# led-bike-suit-controller_v2.net
KiCad netlist of a schematic drawn in EAGLE
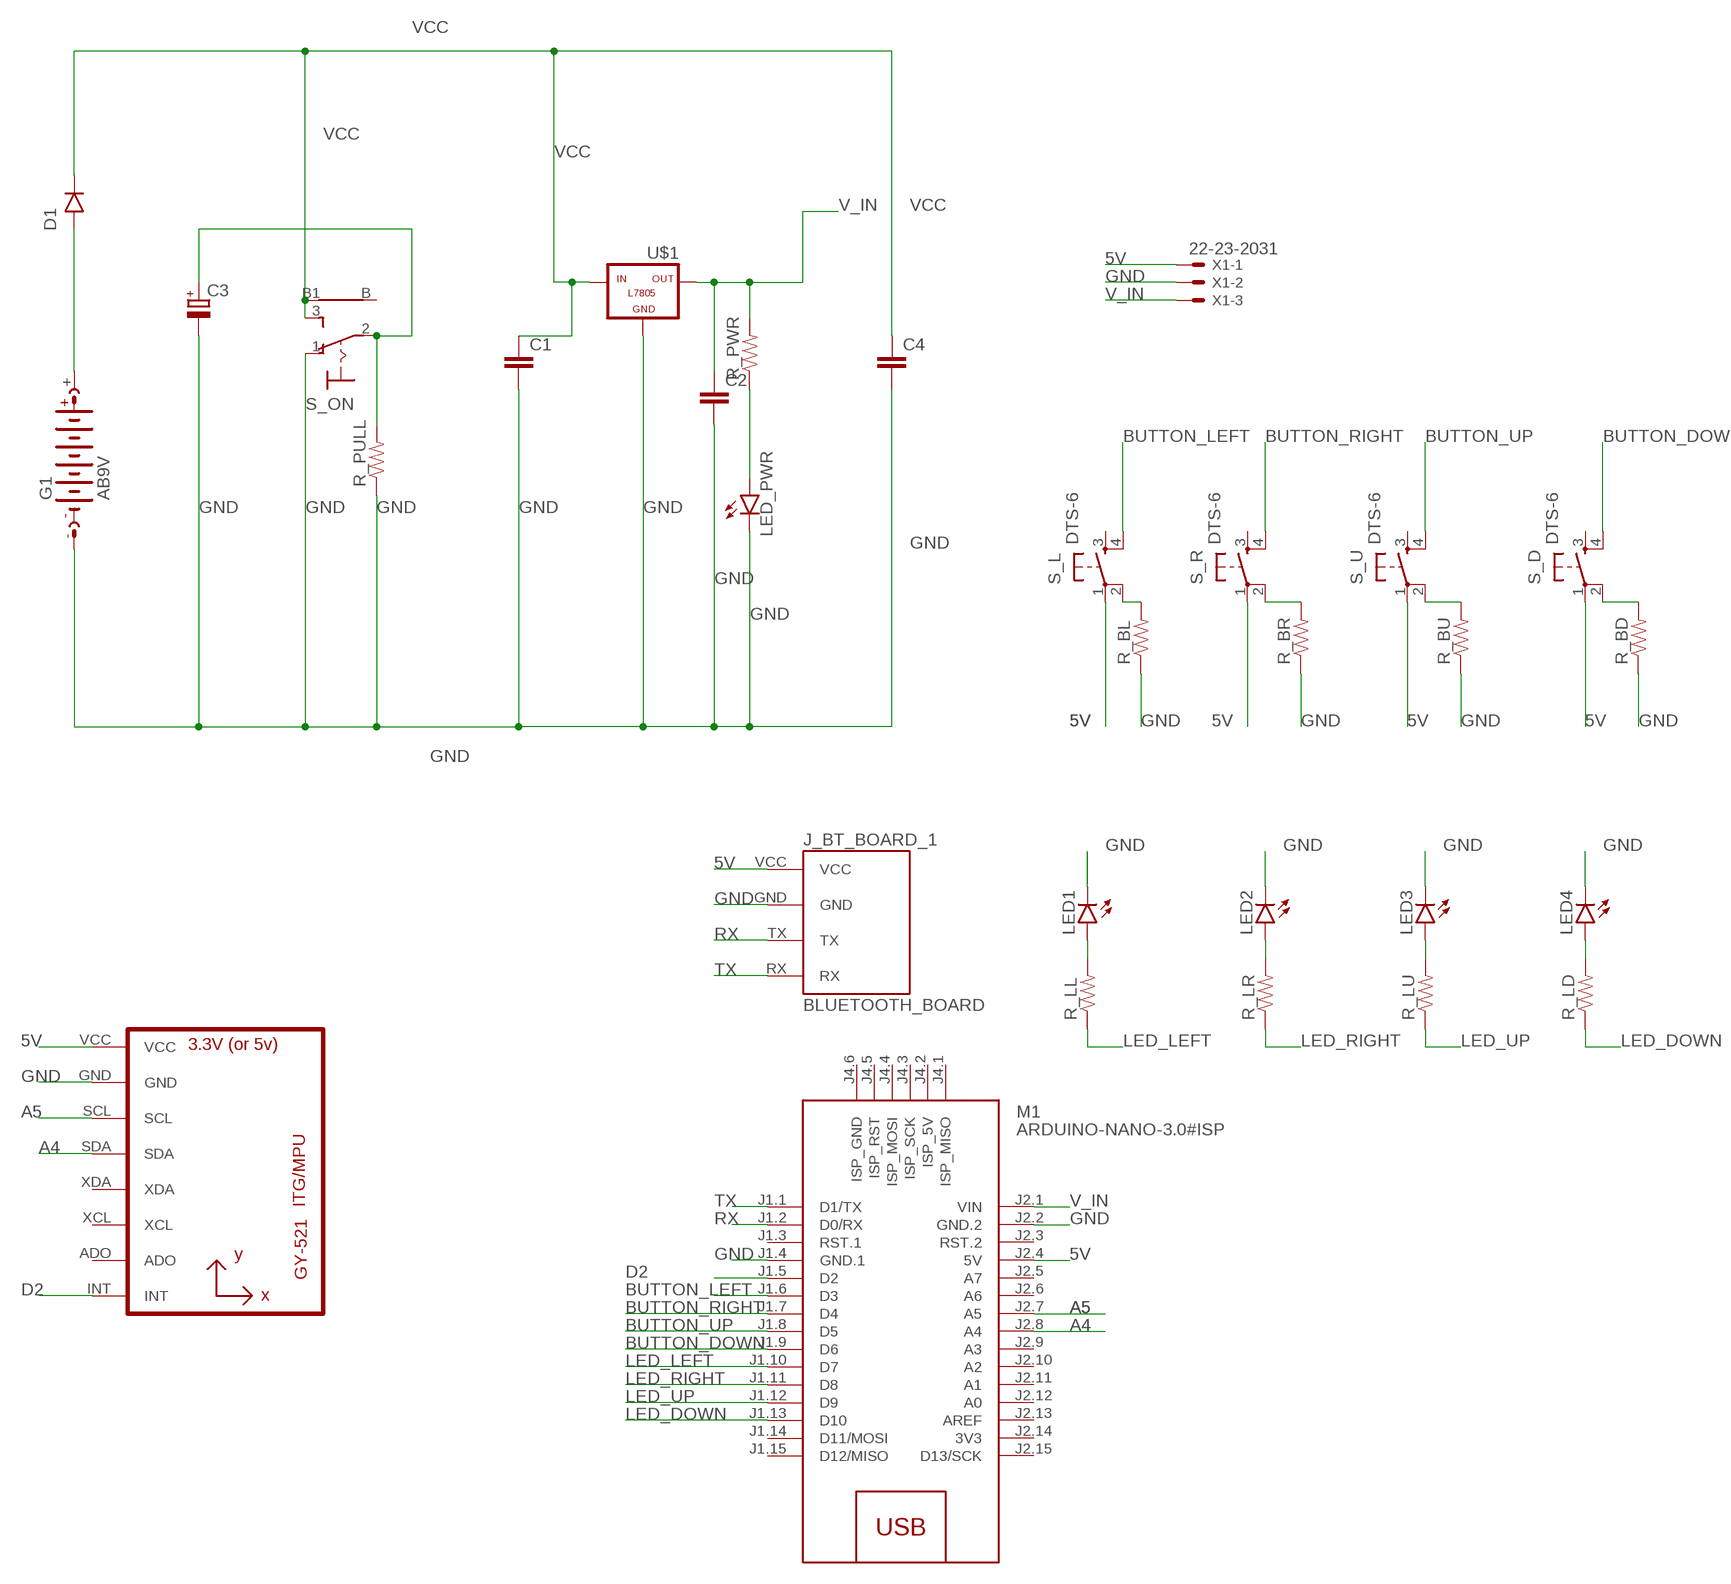
[diagram p0: schematic, sheet 1]

(export (version "E")
  (design (tool "Eeschema 10.0.6"))
  (components
    (comp (ref "C1")
      (value "C2.5/4")
      (footprint "eagle-import:C2.5-4")
      (libsource (lib "eagle-import") (part "C2.5/4"))
    )
    (comp (ref "C2")
      (value "C2.5/4")
      (footprint "eagle-import:C2.5-4")
      (libsource (lib "eagle-import") (part "C2.5/4"))
    )
    (comp (ref "C3")
      (value "RCL_CPOL-EUE3.5-8")
      (footprint "eagle-import:ELECTROLYTIC_CAP_RCL_E3,5-8")
      (libsource (lib "eagle-import") (part "RCL_CPOL-EUE3.5-8"))
    )
    (comp (ref "C4")
      (value "C2.5/4")
      (footprint "eagle-import:C2.5-4")
      (libsource (lib "eagle-import") (part "C2.5/4"))
    )
    (comp (ref "D1")
      (value "1N4001")
      (footprint "eagle-import:DO41-10")
      (libsource (lib "eagle-import") (part "1N4001"))
    )
    (comp (ref "G1")
      (value "AB9V")
      (footprint "eagle-import:AB9V")
      (libsource (lib "eagle-import") (part "AB9V"))
    )
    (comp (ref "J_BT_BOARD_1")
      (value "BLUETOOTH_BOARD")
      (footprint "eagle-import:BT_BOARD_FOOTPRINT")
      (libsource (lib "eagle-import") (part "BLUETOOTH_BOARD"))
    )
    (comp (ref "LED1")
      (value "LED5MM")
      (footprint "eagle-import:SPARKFUN-LED_LED5MM")
      (libsource (lib "eagle-import") (part "LED5MM"))
    )
    (comp (ref "LED2")
      (value "LED5MM")
      (footprint "eagle-import:SPARKFUN-LED_LED5MM")
      (libsource (lib "eagle-import") (part "LED5MM"))
    )
    (comp (ref "LED3")
      (value "LED5MM")
      (footprint "eagle-import:SPARKFUN-LED_LED5MM")
      (libsource (lib "eagle-import") (part "LED5MM"))
    )
    (comp (ref "LED4")
      (value "LED5MM")
      (footprint "eagle-import:SPARKFUN-LED_LED5MM")
      (libsource (lib "eagle-import") (part "LED5MM"))
    )
    (comp (ref "LED_PWR")
      (value "LED5MM")
      (footprint "eagle-import:LED5MM")
      (libsource (lib "eagle-import") (part "tango_LED5MM"))
    )
    (comp (ref "M1")
      (value "ARDUINO-NANO-3.0#ISP")
      (footprint "eagle-import:ARDUINO-NANO-3.0#ISP")
      (libsource (lib "eagle-import") (part "ARDUINO-NANO-3.0#ISP"))
    )
    (comp (ref "R_BD")
      (value "PASSIVES_RESISTORPTH-1/4W")
      (footprint "eagle-import:SPARKFUN-PASSIVES_AXIAL-0.4")
      (libsource (lib "eagle-import") (part "PASSIVES_RESISTORPTH-1/4W"))
    )
    (comp (ref "R_BL")
      (value "PASSIVES_RESISTORPTH-1/4W")
      (footprint "eagle-import:SPARKFUN-PASSIVES_AXIAL-0.4")
      (libsource (lib "eagle-import") (part "PASSIVES_RESISTORPTH-1/4W"))
    )
    (comp (ref "R_BR")
      (value "PASSIVES_RESISTORPTH-1/4W")
      (footprint "eagle-import:SPARKFUN-PASSIVES_AXIAL-0.4")
      (libsource (lib "eagle-import") (part "PASSIVES_RESISTORPTH-1/4W"))
    )
    (comp (ref "R_BU")
      (value "PASSIVES_RESISTORPTH-1/4W")
      (footprint "eagle-import:SPARKFUN-PASSIVES_AXIAL-0.4")
      (libsource (lib "eagle-import") (part "PASSIVES_RESISTORPTH-1/4W"))
    )
    (comp (ref "R_LD")
      (value "PASSIVES_RESISTORPTH-1/4W")
      (footprint "eagle-import:SPARKFUN-PASSIVES_AXIAL-0.4")
      (libsource (lib "eagle-import") (part "PASSIVES_RESISTORPTH-1/4W"))
    )
    (comp (ref "R_LL")
      (value "PASSIVES_RESISTORPTH-1/4W")
      (footprint "eagle-import:SPARKFUN-PASSIVES_AXIAL-0.4")
      (libsource (lib "eagle-import") (part "PASSIVES_RESISTORPTH-1/4W"))
    )
    (comp (ref "R_LR")
      (value "PASSIVES_RESISTORPTH-1/4W")
      (footprint "eagle-import:SPARKFUN-PASSIVES_AXIAL-0.4")
      (libsource (lib "eagle-import") (part "PASSIVES_RESISTORPTH-1/4W"))
    )
    (comp (ref "R_LU")
      (value "PASSIVES_RESISTORPTH-1/4W")
      (footprint "eagle-import:SPARKFUN-PASSIVES_AXIAL-0.4")
      (libsource (lib "eagle-import") (part "PASSIVES_RESISTORPTH-1/4W"))
    )
    (comp (ref "R_PULL")
      (value "PASSIVES_RESISTORPTH-1/4W")
      (footprint "eagle-import:SPARKFUN-PASSIVES_AXIAL-0.4")
      (libsource (lib "eagle-import") (part "PASSIVES_RESISTORPTH-1/4W"))
    )
    (comp (ref "R_PWR")
      (value "PASSIVES_RESISTORPTH-1/4W")
      (footprint "eagle-import:SPARKFUN-PASSIVES_AXIAL-0.4")
      (libsource (lib "eagle-import") (part "PASSIVES_RESISTORPTH-1/4W"))
    )
    (comp (ref "S_D")
      (value "DTS-6")
      (footprint "eagle-import:DTS-6")
      (libsource (lib "eagle-import") (part "DTS-6"))
    )
    (comp (ref "S_L")
      (value "DTS-6")
      (footprint "eagle-import:DTS-6")
      (libsource (lib "eagle-import") (part "DTS-6"))
    )
    (comp (ref "S_ON")
      (value "9070-1W")
      (footprint "eagle-import:9070-1W")
      (libsource (lib "eagle-import") (part "9070-1W"))
    )
    (comp (ref "S_R")
      (value "DTS-6")
      (footprint "eagle-import:DTS-6")
      (libsource (lib "eagle-import") (part "DTS-6"))
    )
    (comp (ref "S_U")
      (value "DTS-6")
      (footprint "eagle-import:DTS-6")
      (libsource (lib "eagle-import") (part "DTS-6"))
    )
    (comp (ref "U$1")
      (value "-L7805")
      (footprint "eagle-import:L7805")
      (libsource (lib "eagle-import") (part "-L7805"))
    )
    (comp (ref "U1")
      (value "GY-521MPU6050")
      (footprint "eagle-import:GY-521")
      (libsource (lib "eagle-import") (part "GY-521MPU6050"))
    )
    (comp (ref "X1")
      (value "22-23-2031")
      (footprint "eagle-import:22-23-2031")
      (fields (field (name "MF") "MOLEX"))
      (libsource (lib "eagle-import") (part "22-23-2031"))
    )
  )
  (nets
    (net (code "1") (name "/3V3") (class "Default")
      (node (ref "M1") (pin "J2.14") (pinfunction "3V3_J2.14") (pintype "power_in"))
    )
    (net (code "2") (name "/5V") (class "Default")
      (node (ref "J_BT_BOARD_1") (pin "VCC") (pinfunction "VCC_VCC") (pintype "bidirectional"))
      (node (ref "M1") (pin "J2.4") (pinfunction "5V_J2.4") (pintype "power_in"))
      (node (ref "S_D") (pin "1") (pinfunction "1_1") (pintype "passive"))
      (node (ref "S_L") (pin "1") (pinfunction "1_1") (pintype "passive"))
      (node (ref "S_R") (pin "1") (pinfunction "1_1") (pintype "passive"))
      (node (ref "S_U") (pin "1") (pinfunction "1_1") (pintype "passive"))
      (node (ref "U1") (pin "VCC") (pinfunction "VCC_VCC") (pintype "bidirectional"))
      (node (ref "X1") (pin "1") (pinfunction "S_1") (pintype "passive"))
    )
    (net (code "3") (name "/A4") (class "Default")
      (node (ref "M1") (pin "J2.8") (pinfunction "A4_J2.8") (pintype "bidirectional"))
      (node (ref "U1") (pin "SDA") (pinfunction "SDA_SDA") (pintype "bidirectional"))
    )
    (net (code "4") (name "/A5") (class "Default")
      (node (ref "M1") (pin "J2.7") (pinfunction "A5_J2.7") (pintype "bidirectional"))
      (node (ref "U1") (pin "SCL") (pinfunction "SCL_SCL") (pintype "bidirectional"))
    )
    (net (code "5") (name "/BUTTON_DOWN") (class "Default")
      (node (ref "M1") (pin "J1.9") (pinfunction "D6_J1.9") (pintype "bidirectional"))
      (node (ref "S_D") (pin "4") (pinfunction "4_4") (pintype "passive"))
    )
    (net (code "6") (name "/BUTTON_LEFT") (class "Default")
      (node (ref "M1") (pin "J1.6") (pinfunction "D3_J1.6") (pintype "bidirectional"))
      (node (ref "S_L") (pin "4") (pinfunction "4_4") (pintype "passive"))
    )
    (net (code "7") (name "/BUTTON_RIGHT") (class "Default")
      (node (ref "M1") (pin "J1.7") (pinfunction "D4_J1.7") (pintype "bidirectional"))
      (node (ref "S_R") (pin "4") (pinfunction "4_4") (pintype "passive"))
    )
    (net (code "8") (name "/BUTTON_UP") (class "Default")
      (node (ref "M1") (pin "J1.8") (pinfunction "D5_J1.8") (pintype "bidirectional"))
      (node (ref "S_U") (pin "4") (pinfunction "4_4") (pintype "passive"))
    )
    (net (code "9") (name "/D2") (class "Default")
      (node (ref "M1") (pin "J1.5") (pinfunction "D2_J1.5") (pintype "bidirectional"))
      (node (ref "U1") (pin "INT") (pinfunction "INT_INT") (pintype "bidirectional"))
    )
    (net (code "10") (name "/GND") (class "Default")
      (node (ref "C1") (pin "2") (pinfunction "2_2") (pintype "passive"))
      (node (ref "C2") (pin "2") (pinfunction "2_2") (pintype "passive"))
      (node (ref "C3") (pin "-") (pinfunction "-_-") (pintype "passive"))
      (node (ref "C4") (pin "2") (pinfunction "2_2") (pintype "passive"))
      (node (ref "G1") (pin "-") (pinfunction "-_-") (pintype "passive"))
      (node (ref "J_BT_BOARD_1") (pin "GND") (pinfunction "GND_GND") (pintype "bidirectional"))
      (node (ref "LED1") (pin "K") (pinfunction "C_K") (pintype "passive"))
      (node (ref "LED2") (pin "K") (pinfunction "C_K") (pintype "passive"))
      (node (ref "LED3") (pin "K") (pinfunction "C_K") (pintype "passive"))
      (node (ref "LED4") (pin "K") (pinfunction "C_K") (pintype "passive"))
      (node (ref "LED_PWR") (pin "K") (pinfunction "CATHODE_K") (pintype "passive"))
      (node (ref "M1") (pin "J1.4") (pinfunction "GND.1_J1.4") (pintype "power_in"))
      (node (ref "M1") (pin "J2.2") (pinfunction "GND.2_J2.2") (pintype "power_in"))
      (node (ref "R_BD") (pin "P$1") (pinfunction "1_P$1") (pintype "passive"))
      (node (ref "R_BL") (pin "P$1") (pinfunction "1_P$1") (pintype "passive"))
      (node (ref "R_BR") (pin "P$1") (pinfunction "1_P$1") (pintype "passive"))
      (node (ref "R_BU") (pin "P$1") (pinfunction "1_P$1") (pintype "passive"))
      (node (ref "R_PULL") (pin "P$1") (pinfunction "1_P$1") (pintype "passive"))
      (node (ref "S_ON") (pin "1") (pinfunction "O_1") (pintype "passive"))
      (node (ref "U$1") (pin "GND") (pinfunction "GND_GND") (pintype "input"))
      (node (ref "U1") (pin "GND") (pinfunction "GND_GND") (pintype "bidirectional"))
      (node (ref "X1") (pin "2") (pinfunction "S_2") (pintype "passive"))
    )
    (net (code "11") (name "/LED_DOWN") (class "Default")
      (node (ref "M1") (pin "J1.13") (pinfunction "D10_J1.13") (pintype "bidirectional"))
      (node (ref "R_LD") (pin "P$1") (pinfunction "1_P$1") (pintype "passive"))
    )
    (net (code "12") (name "/LED_LEFT") (class "Default")
      (node (ref "M1") (pin "J1.10") (pinfunction "D7_J1.10") (pintype "bidirectional"))
      (node (ref "R_LL") (pin "P$1") (pinfunction "1_P$1") (pintype "passive"))
    )
    (net (code "13") (name "/LED_RIGHT") (class "Default")
      (node (ref "M1") (pin "J1.11") (pinfunction "D8_J1.11") (pintype "bidirectional"))
      (node (ref "R_LR") (pin "P$1") (pinfunction "1_P$1") (pintype "passive"))
    )
    (net (code "14") (name "/LED_UP") (class "Default")
      (node (ref "M1") (pin "J1.12") (pinfunction "D9_J1.12") (pintype "bidirectional"))
      (node (ref "R_LU") (pin "P$1") (pinfunction "1_P$1") (pintype "passive"))
    )
    (net (code "15") (name "/RX") (class "Default")
      (node (ref "J_BT_BOARD_1") (pin "TX") (pinfunction "TX_TX") (pintype "bidirectional"))
      (node (ref "M1") (pin "J1.2") (pinfunction "D0/RX_J1.2") (pintype "bidirectional"))
    )
    (net (code "16") (name "/TX") (class "Default")
      (node (ref "J_BT_BOARD_1") (pin "RX") (pinfunction "RX_RX") (pintype "bidirectional"))
      (node (ref "M1") (pin "J1.1") (pinfunction "D1/TX_J1.1") (pintype "bidirectional"))
    )
    (net (code "17") (name "/VCC") (class "Default")
      (node (ref "C1") (pin "1") (pinfunction "1_1") (pintype "passive"))
      (node (ref "C4") (pin "1") (pinfunction "1_1") (pintype "passive"))
      (node (ref "D1") (pin "C") (pinfunction "CATHODE_C") (pintype "passive"))
      (node (ref "S_ON") (pin "3") (pinfunction "S_3") (pintype "passive"))
      (node (ref "S_ON") (pin "B1") (pinfunction "B1_B1") (pintype "passive"))
      (node (ref "U$1") (pin "IN") (pinfunction "IN_IN") (pintype "input"))
    )
    (net (code "18") (name "/V_IN") (class "Default")
      (node (ref "C2") (pin "1") (pinfunction "1_1") (pintype "passive"))
      (node (ref "M1") (pin "J2.1") (pinfunction "VIN_J2.1") (pintype "power_in"))
      (node (ref "R_PWR") (pin "P$2") (pinfunction "2_P$2") (pintype "passive"))
      (node (ref "U$1") (pin "OUT") (pinfunction "OUT_OUT") (pintype "passive"))
      (node (ref "X1") (pin "3") (pinfunction "S_3") (pintype "passive"))
    )
    (net (code "19") (name "Net-(D1-ANODE)") (class "Default")
      (node (ref "D1") (pin "A") (pinfunction "ANODE_A") (pintype "passive"))
      (node (ref "G1") (pin "+") (pinfunction "+_+") (pintype "passive"))
    )
    (net (code "20") (name "Net-(LED_PWR-ANODE)") (class "Default")
      (node (ref "LED_PWR") (pin "A") (pinfunction "ANODE_A") (pintype "passive"))
      (node (ref "R_PWR") (pin "P$1") (pinfunction "1_P$1") (pintype "passive"))
    )
    (net (code "21") (name "Net-(R_BD-2)") (class "Default")
      (node (ref "R_BD") (pin "P$2") (pinfunction "2_P$2") (pintype "passive"))
      (node (ref "S_D") (pin "2") (pinfunction "2_2") (pintype "passive"))
    )
    (net (code "22") (name "Net-(R_BL-2)") (class "Default")
      (node (ref "R_BL") (pin "P$2") (pinfunction "2_P$2") (pintype "passive"))
      (node (ref "S_L") (pin "2") (pinfunction "2_2") (pintype "passive"))
    )
    (net (code "23") (name "Net-(R_BR-2)") (class "Default")
      (node (ref "R_BR") (pin "P$2") (pinfunction "2_P$2") (pintype "passive"))
      (node (ref "S_R") (pin "2") (pinfunction "2_2") (pintype "passive"))
    )
    (net (code "24") (name "Net-(R_BU-2)") (class "Default")
      (node (ref "R_BU") (pin "P$2") (pinfunction "2_P$2") (pintype "passive"))
      (node (ref "S_U") (pin "2") (pinfunction "2_2") (pintype "passive"))
    )
    (net (code "25") (name "Net-(R_LD-2)") (class "Default")
      (node (ref "LED4") (pin "A") (pinfunction "A_A") (pintype "passive"))
      (node (ref "R_LD") (pin "P$2") (pinfunction "2_P$2") (pintype "passive"))
    )
    (net (code "26") (name "Net-(R_LL-2)") (class "Default")
      (node (ref "LED1") (pin "A") (pinfunction "A_A") (pintype "passive"))
      (node (ref "R_LL") (pin "P$2") (pinfunction "2_P$2") (pintype "passive"))
    )
    (net (code "27") (name "Net-(R_LR-2)") (class "Default")
      (node (ref "LED2") (pin "A") (pinfunction "A_A") (pintype "passive"))
      (node (ref "R_LR") (pin "P$2") (pinfunction "2_P$2") (pintype "passive"))
    )
    (net (code "28") (name "Net-(R_LU-2)") (class "Default")
      (node (ref "LED3") (pin "A") (pinfunction "A_A") (pintype "passive"))
      (node (ref "R_LU") (pin "P$2") (pinfunction "2_P$2") (pintype "passive"))
    )
    (net (code "29") (name "Net-(R_PULL-2)") (class "Default")
      (node (ref "C3") (pin "+") (pinfunction "+_+") (pintype "passive"))
      (node (ref "R_PULL") (pin "P$2") (pinfunction "2_P$2") (pintype "passive"))
      (node (ref "S_ON") (pin "2") (pinfunction "P_2") (pintype "passive"))
    )
    (net (code "30") (name "unconnected-(M1-A0-PadJ2.12)") (class "Default")
      (node (ref "M1") (pin "J2.12") (pinfunction "A0_J2.12") (pintype "bidirectional"))
    )
    (net (code "31") (name "unconnected-(M1-A1-PadJ2.11)") (class "Default")
      (node (ref "M1") (pin "J2.11") (pinfunction "A1_J2.11") (pintype "bidirectional"))
    )
    (net (code "32") (name "unconnected-(M1-A2-PadJ2.10)") (class "Default")
      (node (ref "M1") (pin "J2.10") (pinfunction "A2_J2.10") (pintype "bidirectional"))
    )
    (net (code "33") (name "unconnected-(M1-A3-PadJ2.9)") (class "Default")
      (node (ref "M1") (pin "J2.9") (pinfunction "A3_J2.9") (pintype "bidirectional"))
    )
    (net (code "34") (name "unconnected-(M1-A6-PadJ2.6)") (class "Default")
      (node (ref "M1") (pin "J2.6") (pinfunction "A6_J2.6") (pintype "bidirectional"))
    )
    (net (code "35") (name "unconnected-(M1-A7-PadJ2.5)") (class "Default")
      (node (ref "M1") (pin "J2.5") (pinfunction "A7_J2.5") (pintype "bidirectional"))
    )
    (net (code "36") (name "unconnected-(M1-AREF-PadJ2.13)") (class "Default")
      (node (ref "M1") (pin "J2.13") (pinfunction "AREF_J2.13") (pintype "bidirectional"))
    )
    (net (code "37") (name "unconnected-(M1-D11{slash}MOSI-PadJ1.14)") (class "Default")
      (node (ref "M1") (pin "J1.14") (pinfunction "D11/MOSI_J1.14") (pintype "bidirectional"))
    )
    (net (code "38") (name "unconnected-(M1-D12{slash}MISO-PadJ1.15)") (class "Default")
      (node (ref "M1") (pin "J1.15") (pinfunction "D12/MISO_J1.15") (pintype "bidirectional"))
    )
    (net (code "39") (name "unconnected-(M1-D13{slash}SCK-PadJ2.15)") (class "Default")
      (node (ref "M1") (pin "J2.15") (pinfunction "D13/SCK_J2.15") (pintype "bidirectional"))
    )
    (net (code "40") (name "unconnected-(M1-ISP_5V-PadJ4.2)") (class "Default")
      (node (ref "M1") (pin "J4.2") (pinfunction "ISP_5V_J4.2") (pintype "bidirectional"))
    )
    (net (code "41") (name "unconnected-(M1-ISP_GND-PadJ4.6)") (class "Default")
      (node (ref "M1") (pin "J4.6") (pinfunction "ISP_GND_J4.6") (pintype "bidirectional"))
    )
    (net (code "42") (name "unconnected-(M1-ISP_MISO-PadJ4.1)") (class "Default")
      (node (ref "M1") (pin "J4.1") (pinfunction "ISP_MISO_J4.1") (pintype "bidirectional"))
    )
    (net (code "43") (name "unconnected-(M1-ISP_MOSI-PadJ4.4)") (class "Default")
      (node (ref "M1") (pin "J4.4") (pinfunction "ISP_MOSI_J4.4") (pintype "bidirectional"))
    )
    (net (code "44") (name "unconnected-(M1-ISP_RST-PadJ4.5)") (class "Default")
      (node (ref "M1") (pin "J4.5") (pinfunction "ISP_RST_J4.5") (pintype "bidirectional"))
    )
    (net (code "45") (name "unconnected-(M1-ISP_SCK-PadJ4.3)") (class "Default")
      (node (ref "M1") (pin "J4.3") (pinfunction "ISP_SCK_J4.3") (pintype "bidirectional"))
    )
    (net (code "46") (name "unconnected-(M1-RST.1-PadJ1.3)") (class "Default")
      (node (ref "M1") (pin "J1.3") (pinfunction "RST.1_J1.3") (pintype "bidirectional"))
    )
    (net (code "47") (name "unconnected-(M1-RST.2-PadJ2.3)") (class "Default")
      (node (ref "M1") (pin "J2.3") (pinfunction "RST.2_J2.3") (pintype "bidirectional"))
    )
    (net (code "48") (name "unconnected-(S_D-Pad3)") (class "Default")
      (node (ref "S_D") (pin "3") (pinfunction "3_3") (pintype "passive"))
    )
    (net (code "49") (name "unconnected-(S_L-Pad3)") (class "Default")
      (node (ref "S_L") (pin "3") (pinfunction "3_3") (pintype "passive"))
    )
    (net (code "50") (name "unconnected-(S_ON-PadB)") (class "Default")
      (node (ref "S_ON") (pin "B") (pinfunction "B_B") (pintype "passive"))
    )
    (net (code "51") (name "unconnected-(S_R-Pad3)") (class "Default")
      (node (ref "S_R") (pin "3") (pinfunction "3_3") (pintype "passive"))
    )
    (net (code "52") (name "unconnected-(S_U-Pad3)") (class "Default")
      (node (ref "S_U") (pin "3") (pinfunction "3_3") (pintype "passive"))
    )
    (net (code "53") (name "unconnected-(U1-PadADO)") (class "Default")
      (node (ref "U1") (pin "ADO") (pinfunction "ADO_ADO") (pintype "bidirectional"))
    )
    (net (code "54") (name "unconnected-(U1-PadXCL)") (class "Default")
      (node (ref "U1") (pin "XCL") (pinfunction "XCL_XCL") (pintype "bidirectional"))
    )
    (net (code "55") (name "unconnected-(U1-PadXDA)") (class "Default")
      (node (ref "U1") (pin "XDA") (pinfunction "XDA_XDA") (pintype "bidirectional"))
    )
  )
)
